# OpenServoCAN_Encoder_Board_V_1_0_1.net
KiCad netlist of a schematic drawn in EAGLE
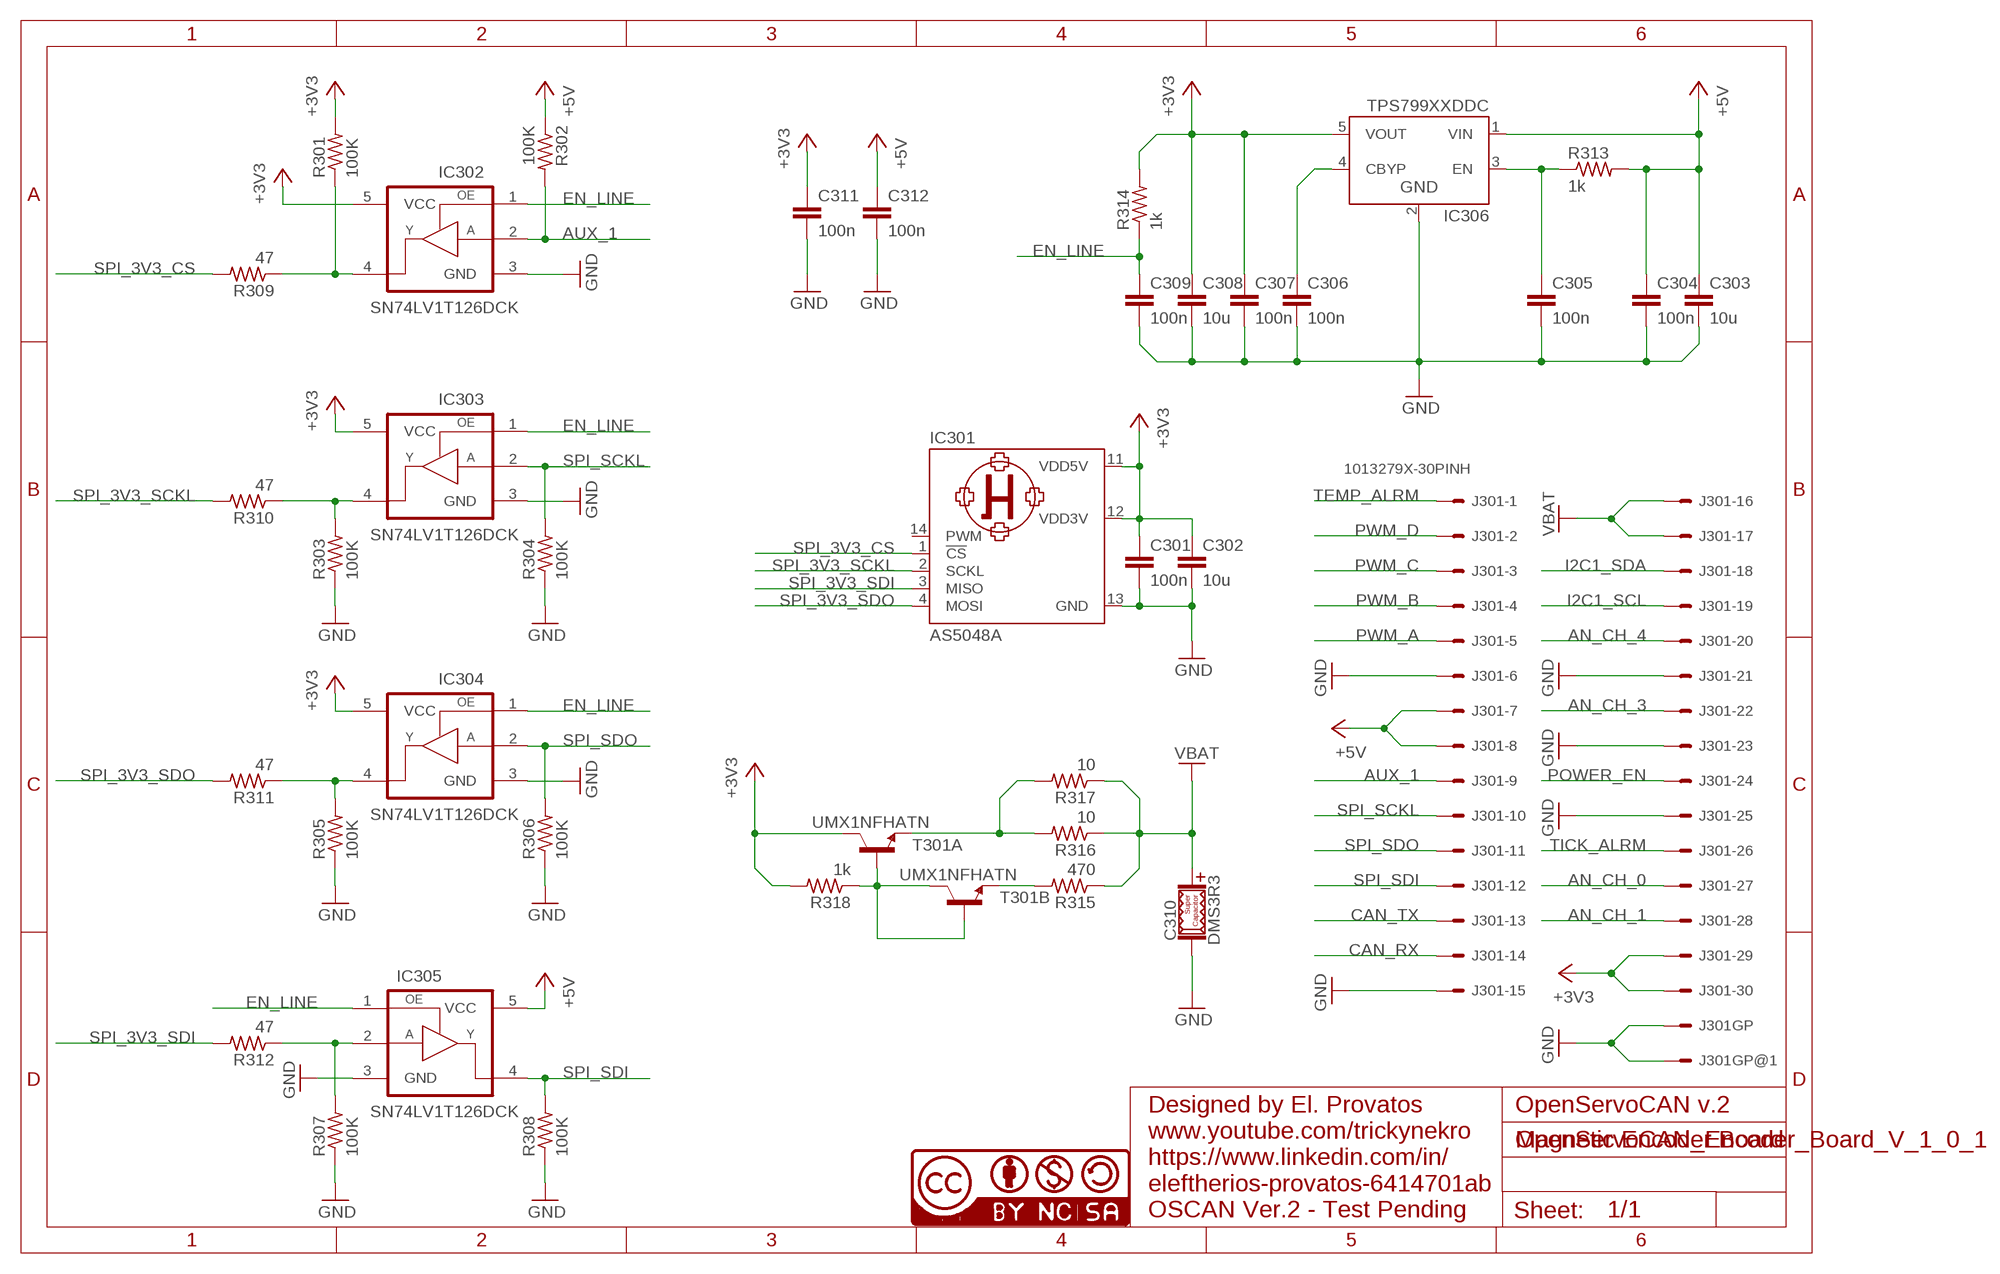
[diagram p0: schematic, sheet 1]

(export (version "E")
  (design (tool "Eeschema 10.0.6"))
  (components
    (comp (ref "C301")
      (value "100n")
      (footprint "eagle-import:0402_C")
      (libsource (lib "eagle-import") (part "C-EUC0402"))
    )
    (comp (ref "C302")
      (value "10u")
      (footprint "eagle-import:0402_C")
      (libsource (lib "eagle-import") (part "C-EUC0402"))
    )
    (comp (ref "C303")
      (value "10u")
      (footprint "eagle-import:0402_C")
      (libsource (lib "eagle-import") (part "C-EUC0402"))
    )
    (comp (ref "C304")
      (value "100n")
      (footprint "eagle-import:0402_C")
      (libsource (lib "eagle-import") (part "C-EUC0402"))
    )
    (comp (ref "C305")
      (value "100n")
      (footprint "eagle-import:0402_C")
      (libsource (lib "eagle-import") (part "C-EUC0402"))
    )
    (comp (ref "C306")
      (value "100n")
      (footprint "eagle-import:0402_C")
      (libsource (lib "eagle-import") (part "C-EUC0402"))
    )
    (comp (ref "C307")
      (value "100n")
      (footprint "eagle-import:0402_C")
      (libsource (lib "eagle-import") (part "C-EUC0402"))
    )
    (comp (ref "C308")
      (value "10u")
      (footprint "eagle-import:0402_C")
      (libsource (lib "eagle-import") (part "C-EUC0402"))
    )
    (comp (ref "C309")
      (value "100n")
      (footprint "eagle-import:0402_C")
      (libsource (lib "eagle-import") (part "C-EUC0402"))
    )
    (comp (ref "C310")
      (value "DMS3R3")
      (footprint "eagle-import:DMS_3R3_S_CAP")
      (libsource (lib "eagle-import") (part "DMS3R3"))
    )
    (comp (ref "C311")
      (value "100n")
      (footprint "eagle-import:0402_C")
      (libsource (lib "eagle-import") (part "C-EUC0402"))
    )
    (comp (ref "C312")
      (value "100n")
      (footprint "eagle-import:0402_C")
      (libsource (lib "eagle-import") (part "C-EUC0402"))
    )
    (comp (ref "IC301")
      (value "AS5048A")
      (footprint "eagle-import:TSSOP-14")
      (libsource (lib "eagle-import") (part "AS5048A"))
    )
    (comp (ref "IC302")
      (value "SN74LV1T126DCK")
      (footprint "eagle-import:SC-70-5")
      (libsource (lib "eagle-import") (part "SN74LV1T126DCK"))
    )
    (comp (ref "IC303")
      (value "SN74LV1T126DCK")
      (footprint "eagle-import:SC-70-5")
      (libsource (lib "eagle-import") (part "SN74LV1T126DCK"))
    )
    (comp (ref "IC304")
      (value "SN74LV1T126DCK")
      (footprint "eagle-import:SC-70-5")
      (libsource (lib "eagle-import") (part "SN74LV1T126DCK"))
    )
    (comp (ref "IC305")
      (value "SN74LV1T126DCK")
      (footprint "eagle-import:SC-70-5")
      (libsource (lib "eagle-import") (part "SN74LV1T126DCK"))
    )
    (comp (ref "IC306")
      (value "TPS799XXDDC")
      (footprint "eagle-import:SOT-23-5")
      (libsource (lib "eagle-import") (part "TPS799XXDDC"))
    )
    (comp (ref "J301")
      (value "1013279X-30PINH")
      (footprint "eagle-import:10132797-30")
      (libsource (lib "eagle-import") (part "1013279X-30PINH"))
    )
    (comp (ref "R301")
      (value "100K")
      (footprint "eagle-import:0402_R")
      (libsource (lib "eagle-import") (part "R-USR0402"))
    )
    (comp (ref "R302")
      (value "100K")
      (footprint "eagle-import:0402_R")
      (libsource (lib "eagle-import") (part "R-USR0402"))
    )
    (comp (ref "R303")
      (value "100K")
      (footprint "eagle-import:0402_R")
      (libsource (lib "eagle-import") (part "R-USR0402"))
    )
    (comp (ref "R304")
      (value "100K")
      (footprint "eagle-import:0402_R")
      (libsource (lib "eagle-import") (part "R-USR0402"))
    )
    (comp (ref "R305")
      (value "100K")
      (footprint "eagle-import:0402_R")
      (libsource (lib "eagle-import") (part "R-USR0402"))
    )
    (comp (ref "R306")
      (value "100K")
      (footprint "eagle-import:0402_R")
      (libsource (lib "eagle-import") (part "R-USR0402"))
    )
    (comp (ref "R307")
      (value "100K")
      (footprint "eagle-import:0402_R")
      (libsource (lib "eagle-import") (part "R-USR0402"))
    )
    (comp (ref "R308")
      (value "100K")
      (footprint "eagle-import:0402_R")
      (libsource (lib "eagle-import") (part "R-USR0402"))
    )
    (comp (ref "R309")
      (value "47")
      (footprint "eagle-import:0402_R")
      (libsource (lib "eagle-import") (part "R-USR0402"))
    )
    (comp (ref "R310")
      (value "47")
      (footprint "eagle-import:0402_R")
      (libsource (lib "eagle-import") (part "R-USR0402"))
    )
    (comp (ref "R311")
      (value "47")
      (footprint "eagle-import:0402_R")
      (libsource (lib "eagle-import") (part "R-USR0402"))
    )
    (comp (ref "R312")
      (value "47")
      (footprint "eagle-import:0402_R")
      (libsource (lib "eagle-import") (part "R-USR0402"))
    )
    (comp (ref "R313")
      (value "1k")
      (footprint "eagle-import:0402_R")
      (libsource (lib "eagle-import") (part "R-USR0402"))
    )
    (comp (ref "R314")
      (value "1k")
      (footprint "eagle-import:0402_R")
      (libsource (lib "eagle-import") (part "R-USR0402"))
    )
    (comp (ref "R315")
      (value "470")
      (footprint "eagle-import:0402_R")
      (libsource (lib "eagle-import") (part "R-USR0402"))
    )
    (comp (ref "R316")
      (value "10")
      (footprint "eagle-import:0402_R")
      (libsource (lib "eagle-import") (part "R-USR0402"))
    )
    (comp (ref "R317")
      (value "10")
      (footprint "eagle-import:0402_R")
      (libsource (lib "eagle-import") (part "R-USR0402"))
    )
    (comp (ref "R318")
      (value "1k")
      (footprint "eagle-import:0402_R")
      (libsource (lib "eagle-import") (part "R-USR0402"))
    )
    (comp (ref "T301")
      (value "UMX1NFHATN")
      (footprint "eagle-import:SC-70-6")
      (libsource (lib "eagle-import") (part "UMX1NFHATN"))
    )
    (comp (ref "U$1")
      (value "CC-NC-BCNIX")
      (footprint "eagle-import:CC-NC-B_NIX")
      (libsource (lib "eagle-import") (part "CC-NC-BCNIX"))
    )
  )
  (nets
    (net (code "1") (name "+3V3") (class "Default")
      (node (ref "C301") (pin "1") (pinfunction "1_1") (pintype "passive"))
      (node (ref "C302") (pin "1") (pinfunction "1_1") (pintype "passive"))
      (node (ref "C307") (pin "1") (pinfunction "1_1") (pintype "passive"))
      (node (ref "C308") (pin "1") (pinfunction "1_1") (pintype "passive"))
      (node (ref "C311") (pin "1") (pinfunction "1_1") (pintype "passive"))
      (node (ref "IC301") (pin "11") (pinfunction "VDD5V_11") (pintype "bidirectional"))
      (node (ref "IC301") (pin "12") (pinfunction "VDD3V_12") (pintype "bidirectional"))
      (node (ref "IC302") (pin "5") (pinfunction "VCC_5") (pintype "power_in"))
      (node (ref "IC303") (pin "5") (pinfunction "VCC_5") (pintype "power_in"))
      (node (ref "IC304") (pin "5") (pinfunction "VCC_5") (pintype "power_in"))
      (node (ref "IC306") (pin "5") (pinfunction "VOUT_5") (pintype "bidirectional"))
      (node (ref "J301") (pin "29") (pinfunction "S_29") (pintype "passive"))
      (node (ref "J301") (pin "30") (pinfunction "S_30") (pintype "passive"))
      (node (ref "R301") (pin "2") (pinfunction "2_2") (pintype "passive"))
      (node (ref "R314") (pin "2") (pinfunction "2_2") (pintype "passive"))
      (node (ref "R318") (pin "2") (pinfunction "2_2") (pintype "passive"))
      (node (ref "T301") (pin "6") (pinfunction "C_6") (pintype "passive"))
    )
    (net (code "2") (name "+5V") (class "Default")
      (node (ref "C303") (pin "1") (pinfunction "1_1") (pintype "passive"))
      (node (ref "C304") (pin "1") (pinfunction "1_1") (pintype "passive"))
      (node (ref "C312") (pin "1") (pinfunction "1_1") (pintype "passive"))
      (node (ref "IC305") (pin "5") (pinfunction "VCC_5") (pintype "power_in"))
      (node (ref "IC306") (pin "1") (pinfunction "VIN_1") (pintype "bidirectional"))
      (node (ref "J301") (pin "7") (pinfunction "S_7") (pintype "passive"))
      (node (ref "J301") (pin "8") (pinfunction "S_8") (pintype "passive"))
      (node (ref "R302") (pin "1") (pinfunction "1_1") (pintype "passive"))
      (node (ref "R313") (pin "2") (pinfunction "2_2") (pintype "passive"))
    )
    (net (code "3") (name "/AN_CH_0") (class "Default")
      (node (ref "J301") (pin "27") (pinfunction "S_27") (pintype "passive"))
    )
    (net (code "4") (name "/AN_CH_1") (class "Default")
      (node (ref "J301") (pin "28") (pinfunction "S_28") (pintype "passive"))
    )
    (net (code "5") (name "/AN_CH_3") (class "Default")
      (node (ref "J301") (pin "22") (pinfunction "S_22") (pintype "passive"))
    )
    (net (code "6") (name "/AN_CH_4") (class "Default")
      (node (ref "J301") (pin "20") (pinfunction "S_20") (pintype "passive"))
    )
    (net (code "7") (name "/AUX_1") (class "Default")
      (node (ref "IC302") (pin "2") (pinfunction "A_2") (pintype "input"))
      (node (ref "J301") (pin "9") (pinfunction "S_9") (pintype "passive"))
      (node (ref "R302") (pin "2") (pinfunction "2_2") (pintype "passive"))
    )
    (net (code "8") (name "/CAN_RX") (class "Default")
      (node (ref "J301") (pin "14") (pinfunction "S_14") (pintype "passive"))
    )
    (net (code "9") (name "/CAN_TX") (class "Default")
      (node (ref "J301") (pin "13") (pinfunction "S_13") (pintype "passive"))
    )
    (net (code "10") (name "/EN_LINE") (class "Default")
      (node (ref "C309") (pin "1") (pinfunction "1_1") (pintype "passive"))
      (node (ref "IC302") (pin "1") (pinfunction "OE_1") (pintype "input"))
      (node (ref "IC303") (pin "1") (pinfunction "OE_1") (pintype "input"))
      (node (ref "IC304") (pin "1") (pinfunction "OE_1") (pintype "input"))
      (node (ref "IC305") (pin "1") (pinfunction "OE_1") (pintype "input"))
      (node (ref "R314") (pin "1") (pinfunction "1_1") (pintype "passive"))
    )
    (net (code "11") (name "/I2C1_SCL") (class "Default")
      (node (ref "J301") (pin "19") (pinfunction "S_19") (pintype "passive"))
    )
    (net (code "12") (name "/I2C1_SDA") (class "Default")
      (node (ref "J301") (pin "18") (pinfunction "S_18") (pintype "passive"))
    )
    (net (code "13") (name "/POWER_EN") (class "Default")
      (node (ref "J301") (pin "24") (pinfunction "S_24") (pintype "passive"))
    )
    (net (code "14") (name "/PWM_A") (class "Default")
      (node (ref "J301") (pin "5") (pinfunction "S_5") (pintype "passive"))
    )
    (net (code "15") (name "/PWM_B") (class "Default")
      (node (ref "J301") (pin "4") (pinfunction "S_4") (pintype "passive"))
    )
    (net (code "16") (name "/PWM_C") (class "Default")
      (node (ref "J301") (pin "3") (pinfunction "S_3") (pintype "passive"))
    )
    (net (code "17") (name "/PWM_D") (class "Default")
      (node (ref "J301") (pin "2") (pinfunction "S_2") (pintype "passive"))
    )
    (net (code "18") (name "/SPI_3V3_CS") (class "Default")
      (node (ref "IC301") (pin "1") (pinfunction "~{CS}_1") (pintype "bidirectional"))
      (node (ref "R309") (pin "2") (pinfunction "2_2") (pintype "passive"))
    )
    (net (code "19") (name "/SPI_3V3_SCKL") (class "Default")
      (node (ref "IC301") (pin "2") (pinfunction "SCKL_2") (pintype "bidirectional"))
      (node (ref "R310") (pin "2") (pinfunction "2_2") (pintype "passive"))
    )
    (net (code "20") (name "/SPI_3V3_SDI") (class "Default")
      (node (ref "IC301") (pin "3") (pinfunction "MISO_3") (pintype "bidirectional"))
      (node (ref "R312") (pin "2") (pinfunction "2_2") (pintype "passive"))
    )
    (net (code "21") (name "/SPI_3V3_SDO") (class "Default")
      (node (ref "IC301") (pin "4") (pinfunction "MOSI_4") (pintype "bidirectional"))
      (node (ref "R311") (pin "2") (pinfunction "2_2") (pintype "passive"))
    )
    (net (code "22") (name "/SPI_SCKL") (class "Default")
      (node (ref "IC303") (pin "2") (pinfunction "A_2") (pintype "input"))
      (node (ref "J301") (pin "10") (pinfunction "S_10") (pintype "passive"))
      (node (ref "R304") (pin "2") (pinfunction "2_2") (pintype "passive"))
    )
    (net (code "23") (name "/SPI_SDI") (class "Default")
      (node (ref "IC305") (pin "4") (pinfunction "Y_4") (pintype "output"))
      (node (ref "J301") (pin "12") (pinfunction "S_12") (pintype "passive"))
      (node (ref "R308") (pin "2") (pinfunction "2_2") (pintype "passive"))
    )
    (net (code "24") (name "/SPI_SDO") (class "Default")
      (node (ref "IC304") (pin "2") (pinfunction "A_2") (pintype "input"))
      (node (ref "J301") (pin "11") (pinfunction "S_11") (pintype "passive"))
      (node (ref "R306") (pin "2") (pinfunction "2_2") (pintype "passive"))
    )
    (net (code "25") (name "/TEMP_ALRM") (class "Default")
      (node (ref "J301") (pin "1") (pinfunction "S_1") (pintype "passive"))
    )
    (net (code "26") (name "/TICK_ALRM") (class "Default")
      (node (ref "J301") (pin "26") (pinfunction "S_26") (pintype "passive"))
    )
    (net (code "27") (name "GND") (class "Default")
      (node (ref "C301") (pin "2") (pinfunction "2_2") (pintype "passive"))
      (node (ref "C302") (pin "2") (pinfunction "2_2") (pintype "passive"))
      (node (ref "C303") (pin "2") (pinfunction "2_2") (pintype "passive"))
      (node (ref "C304") (pin "2") (pinfunction "2_2") (pintype "passive"))
      (node (ref "C305") (pin "2") (pinfunction "2_2") (pintype "passive"))
      (node (ref "C306") (pin "2") (pinfunction "2_2") (pintype "passive"))
      (node (ref "C307") (pin "2") (pinfunction "2_2") (pintype "passive"))
      (node (ref "C308") (pin "2") (pinfunction "2_2") (pintype "passive"))
      (node (ref "C309") (pin "2") (pinfunction "2_2") (pintype "passive"))
      (node (ref "C310") (pin "NEG-") (pinfunction "NEG_NEG-") (pintype "passive"))
      (node (ref "C311") (pin "2") (pinfunction "2_2") (pintype "passive"))
      (node (ref "C312") (pin "2") (pinfunction "2_2") (pintype "passive"))
      (node (ref "IC301") (pin "13") (pinfunction "GND_13") (pintype "bidirectional"))
      (node (ref "IC302") (pin "3") (pinfunction "GND_3") (pintype "power_in"))
      (node (ref "IC303") (pin "3") (pinfunction "GND_3") (pintype "power_in"))
      (node (ref "IC304") (pin "3") (pinfunction "GND_3") (pintype "power_in"))
      (node (ref "IC305") (pin "3") (pinfunction "GND_3") (pintype "power_in"))
      (node (ref "IC306") (pin "2") (pinfunction "GND_2") (pintype "bidirectional"))
      (node (ref "J301") (pin "15") (pinfunction "S_15") (pintype "passive"))
      (node (ref "J301") (pin "21") (pinfunction "S_21") (pintype "passive"))
      (node (ref "J301") (pin "23") (pinfunction "S_23") (pintype "passive"))
      (node (ref "J301") (pin "25") (pinfunction "S_25") (pintype "passive"))
      (node (ref "J301") (pin "6") (pinfunction "S_6") (pintype "passive"))
      (node (ref "J301") (pin "EP@2") (pinfunction "S_EP@2") (pintype "passive"))
      (node (ref "J301") (pin "EP@↑1") (pinfunction "S_EP@↑1") (pintype "passive"))
      (node (ref "R303") (pin "1") (pinfunction "1_1") (pintype "passive"))
      (node (ref "R304") (pin "1") (pinfunction "1_1") (pintype "passive"))
      (node (ref "R305") (pin "1") (pinfunction "1_1") (pintype "passive"))
      (node (ref "R306") (pin "1") (pinfunction "1_1") (pintype "passive"))
      (node (ref "R307") (pin "1") (pinfunction "1_1") (pintype "passive"))
      (node (ref "R308") (pin "1") (pinfunction "1_1") (pintype "passive"))
    )
    (net (code "28") (name "Net-(IC302-Y)") (class "Default")
      (node (ref "IC302") (pin "4") (pinfunction "Y_4") (pintype "output"))
      (node (ref "R301") (pin "1") (pinfunction "1_1") (pintype "passive"))
      (node (ref "R309") (pin "1") (pinfunction "1_1") (pintype "passive"))
    )
    (net (code "29") (name "Net-(IC303-Y)") (class "Default")
      (node (ref "IC303") (pin "4") (pinfunction "Y_4") (pintype "output"))
      (node (ref "R303") (pin "2") (pinfunction "2_2") (pintype "passive"))
      (node (ref "R310") (pin "1") (pinfunction "1_1") (pintype "passive"))
    )
    (net (code "30") (name "Net-(IC304-Y)") (class "Default")
      (node (ref "IC304") (pin "4") (pinfunction "Y_4") (pintype "output"))
      (node (ref "R305") (pin "2") (pinfunction "2_2") (pintype "passive"))
      (node (ref "R311") (pin "1") (pinfunction "1_1") (pintype "passive"))
    )
    (net (code "31") (name "Net-(IC305-A)") (class "Default")
      (node (ref "IC305") (pin "2") (pinfunction "A_2") (pintype "input"))
      (node (ref "R307") (pin "2") (pinfunction "2_2") (pintype "passive"))
      (node (ref "R312") (pin "1") (pinfunction "1_1") (pintype "passive"))
    )
    (net (code "32") (name "Net-(IC306-CBYP)") (class "Default")
      (node (ref "C306") (pin "1") (pinfunction "1_1") (pintype "passive"))
      (node (ref "IC306") (pin "4") (pinfunction "CBYP_4") (pintype "bidirectional"))
    )
    (net (code "33") (name "Net-(IC306-EN)") (class "Default")
      (node (ref "C305") (pin "1") (pinfunction "1_1") (pintype "passive"))
      (node (ref "IC306") (pin "3") (pinfunction "EN_3") (pintype "bidirectional"))
      (node (ref "R313") (pin "1") (pinfunction "1_1") (pintype "passive"))
    )
    (net (code "34") (name "Net-(T301A-B)") (class "Default")
      (node (ref "R318") (pin "1") (pinfunction "1_1") (pintype "passive"))
      (node (ref "T301") (pin "2") (pinfunction "B_2") (pintype "passive"))
      (node (ref "T301") (pin "3") (pinfunction "C_3") (pintype "passive"))
      (node (ref "T301") (pin "5") (pinfunction "B_5") (pintype "passive"))
    )
    (net (code "35") (name "Net-(T301A-E)") (class "Default")
      (node (ref "R316") (pin "2") (pinfunction "2_2") (pintype "passive"))
      (node (ref "R317") (pin "2") (pinfunction "2_2") (pintype "passive"))
      (node (ref "T301") (pin "1") (pinfunction "E_1") (pintype "passive"))
    )
    (net (code "36") (name "Net-(T301B-E)") (class "Default")
      (node (ref "R315") (pin "2") (pinfunction "2_2") (pintype "passive"))
      (node (ref "T301") (pin "4") (pinfunction "E_4") (pintype "passive"))
    )
    (net (code "37") (name "VBAT") (class "Default")
      (node (ref "C310") (pin "POS+") (pinfunction "POS_POS+") (pintype "passive"))
      (node (ref "J301") (pin "16") (pinfunction "S_16") (pintype "passive"))
      (node (ref "J301") (pin "17") (pinfunction "S_17") (pintype "passive"))
      (node (ref "R315") (pin "1") (pinfunction "1_1") (pintype "passive"))
      (node (ref "R316") (pin "1") (pinfunction "1_1") (pintype "passive"))
      (node (ref "R317") (pin "1") (pinfunction "1_1") (pintype "passive"))
    )
    (net (code "38") (name "unconnected-(IC301A-PWM-Pad14)") (class "Default")
      (node (ref "IC301") (pin "14") (pinfunction "PWM_14") (pintype "bidirectional"))
    )
  )
)
